# autoroute.net
KiCad netlist of a schematic drawn in EAGLE
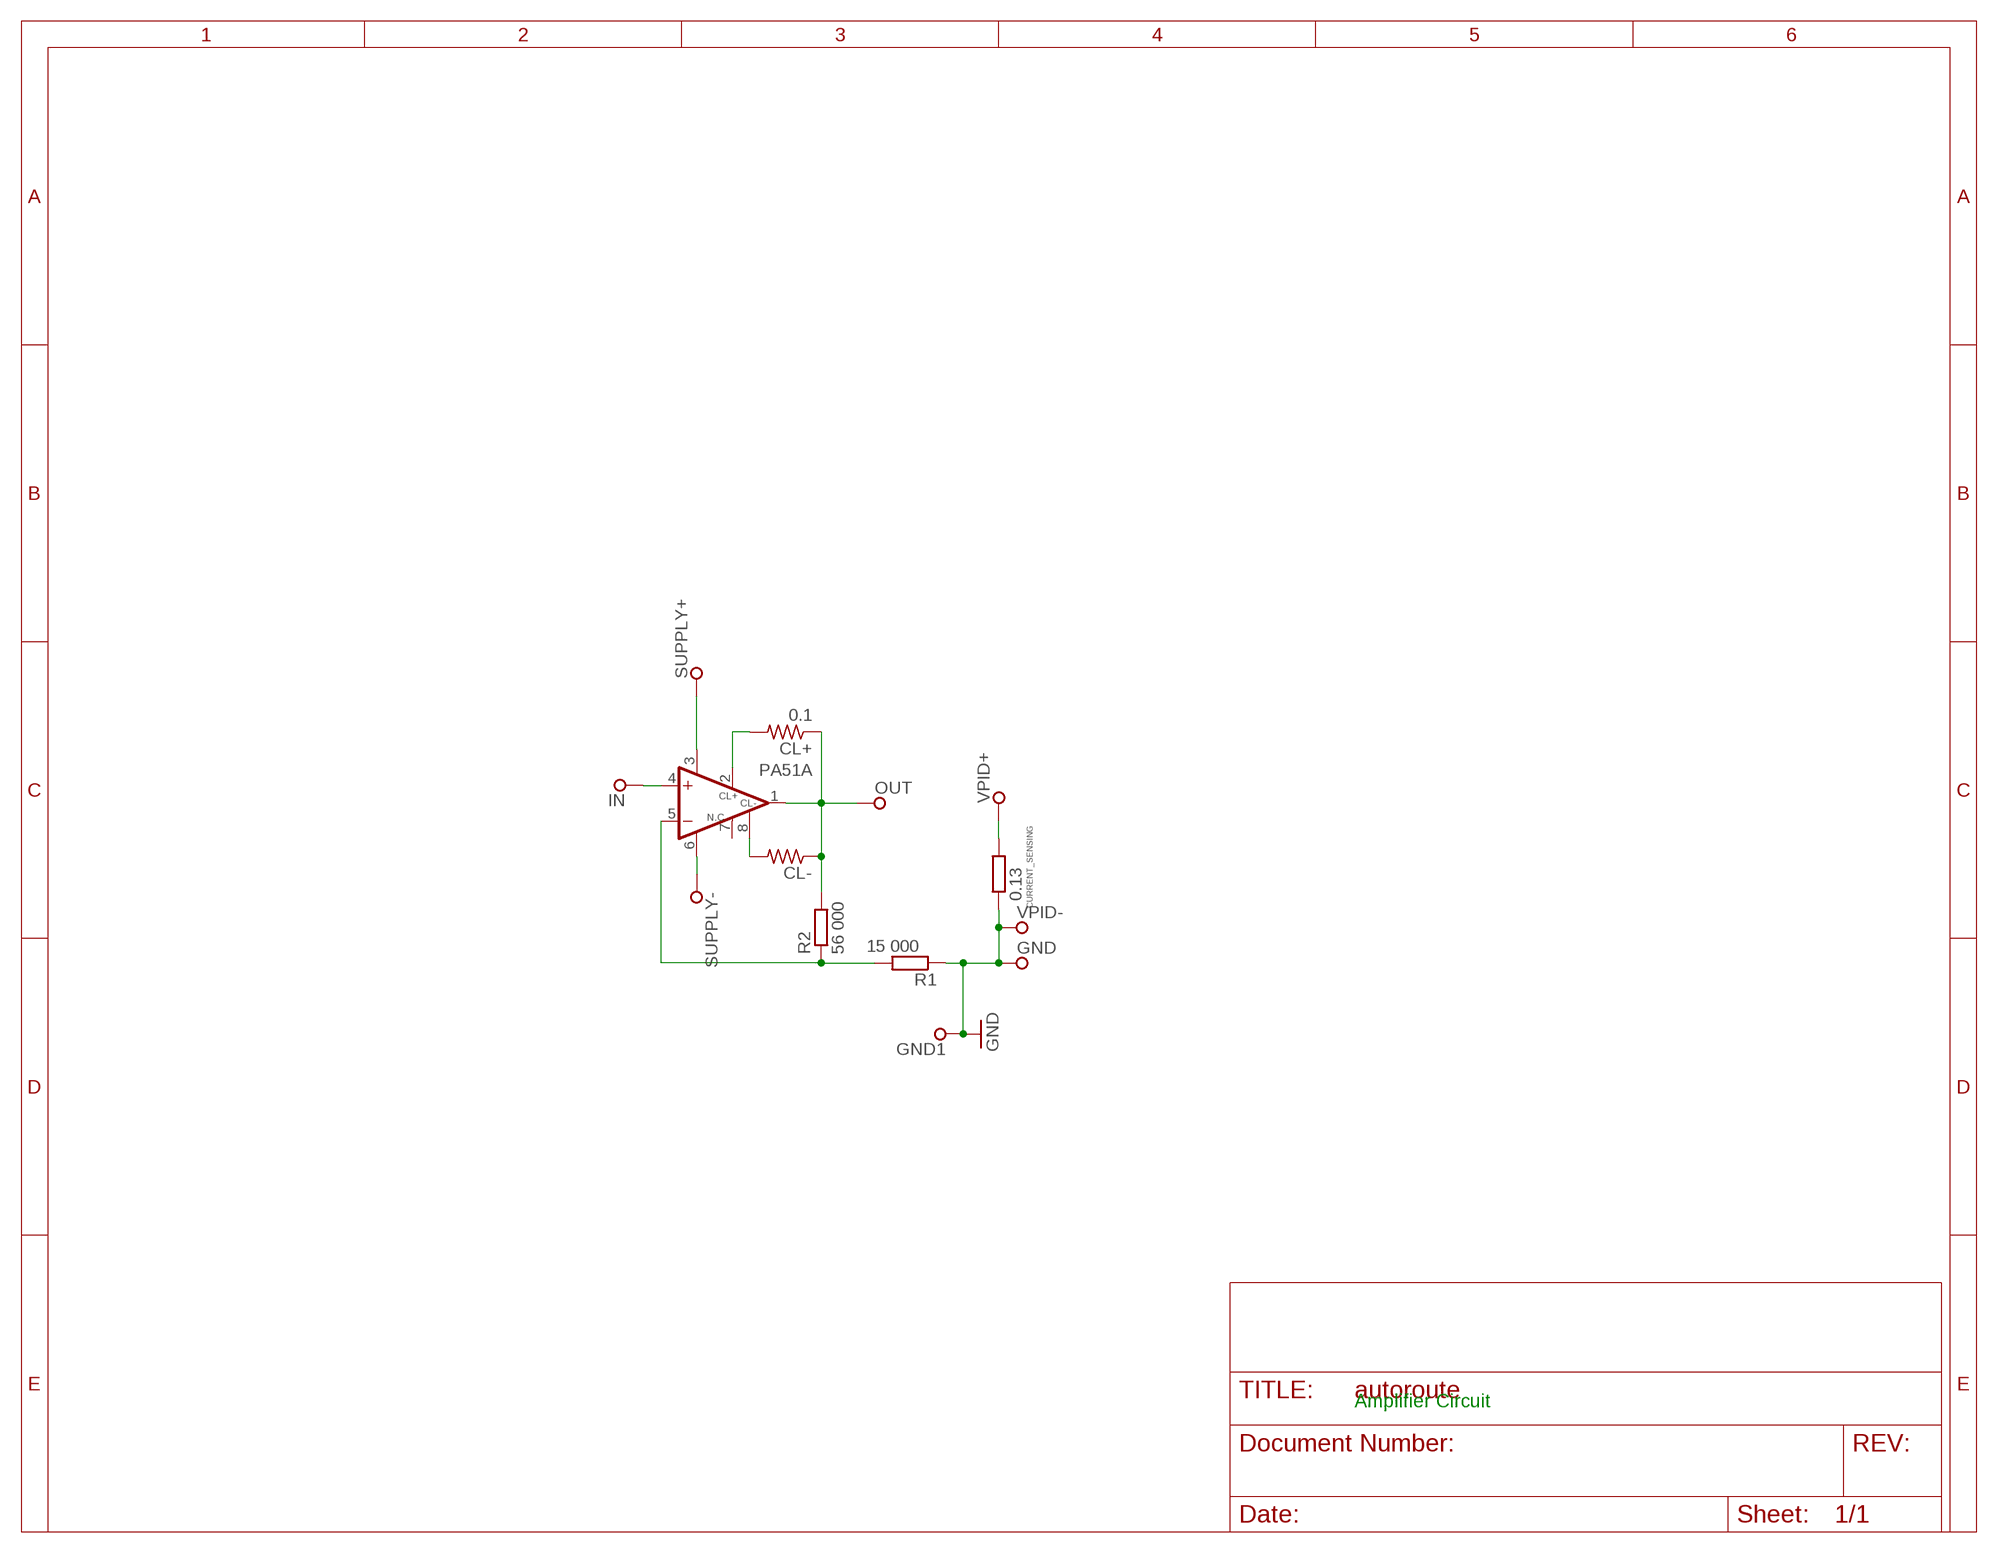
[diagram p0: schematic, sheet 1]

(export (version "E")
  (design (tool "Eeschema 10.0.6"))
  (components
    (comp (ref "CL+")
      (value "0.1")
      (footprint "eagle-import:VTA56")
      (libsource (lib "eagle-import") (part "R-US_VTA56"))
    )
    (comp (ref "CL-")
      (value "R-US_VTA56")
      (footprint "eagle-import:VTA56")
      (libsource (lib "eagle-import") (part "R-US_VTA56"))
    )
    (comp (ref "CURRENT_SENSING")
      (value "0.13")
      (footprint "eagle-import:V234_12")
      (libsource (lib "eagle-import") (part "R-EU_V234/12"))
    )
    (comp (ref "GND")
      (value "SPECIAL_DRILL_0.2500")
      (footprint "eagle-import:PAD_0.2500")
      (libsource (lib "eagle-import") (part "SPECIAL_DRILL_0.2500"))
    )
    (comp (ref "GND1")
      (value "SPECIAL_DRILL_0.2500")
      (footprint "eagle-import:PAD_0.2500")
      (libsource (lib "eagle-import") (part "SPECIAL_DRILL_0.2500"))
    )
    (comp (ref "IN")
      (value "SPECIAL_DRILL_0.2500")
      (footprint "eagle-import:PAD_0.2500")
      (libsource (lib "eagle-import") (part "SPECIAL_DRILL_0.2500"))
    )
    (comp (ref "OUT")
      (value "SPECIAL_DRILL_0.2500")
      (footprint "eagle-import:PAD_0.2500")
      (libsource (lib "eagle-import") (part "SPECIAL_DRILL_0.2500"))
    )
    (comp (ref "R1")
      (value "15 000")
      (footprint "eagle-import:V234_12")
      (libsource (lib "eagle-import") (part "R-EU_V234/12"))
    )
    (comp (ref "R2")
      (value "56 000")
      (footprint "eagle-import:V234_12")
      (libsource (lib "eagle-import") (part "R-EU_V234/12"))
    )
    (comp (ref "SUPPLY+")
      (value "SPECIAL_DRILL_0.2500")
      (footprint "eagle-import:PAD_0.2500")
      (libsource (lib "eagle-import") (part "SPECIAL_DRILL_0.2500"))
    )
    (comp (ref "SUPPLY-")
      (value "SPECIAL_DRILL_0.2500")
      (footprint "eagle-import:PAD_0.2500")
      (libsource (lib "eagle-import") (part "SPECIAL_DRILL_0.2500"))
    )
    (comp (ref "U$1")
      (value "PA51A")
      (footprint "eagle-import:0804MC")
      (libsource (lib "eagle-import") (part "PA51A"))
    )
    (comp (ref "VPID+")
      (value "SPECIAL_DRILL_0.2500")
      (footprint "eagle-import:PAD_0.2500")
      (libsource (lib "eagle-import") (part "SPECIAL_DRILL_0.2500"))
    )
    (comp (ref "VPID-")
      (value "SPECIAL_DRILL_0.2500")
      (footprint "eagle-import:PAD_0.2500")
      (libsource (lib "eagle-import") (part "SPECIAL_DRILL_0.2500"))
    )
  )
  (nets
    (net (code "1") (name "GND") (class "Default")
      (node (ref "CURRENT_SENSING") (pin "1") (pinfunction "1_1") (pintype "passive"))
      (node (ref "GND") (pin "1") (pinfunction "1_1") (pintype "passive"))
      (node (ref "GND1") (pin "1") (pinfunction "1_1") (pintype "passive"))
      (node (ref "R1") (pin "1") (pinfunction "1_1") (pintype "passive"))
      (node (ref "VPID-") (pin "1") (pinfunction "1_1") (pintype "passive"))
    )
    (net (code "2") (name "Net-(CURRENT_SENSING-Pad2)") (class "Default")
      (node (ref "CURRENT_SENSING") (pin "2") (pinfunction "2_2") (pintype "passive"))
      (node (ref "VPID+") (pin "1") (pinfunction "1_1") (pintype "passive"))
    )
    (net (code "3") (name "Net-(U$1-+IN)") (class "Default")
      (node (ref "IN") (pin "1") (pinfunction "1_1") (pintype "passive"))
      (node (ref "U$1") (pin "4") (pinfunction "+IN_4") (pintype "input"))
    )
    (net (code "4") (name "Net-(U$1--IN)") (class "Default")
      (node (ref "R1") (pin "2") (pinfunction "2_2") (pintype "passive"))
      (node (ref "R2") (pin "1") (pinfunction "1_1") (pintype "passive"))
      (node (ref "U$1") (pin "5") (pinfunction "-IN_5") (pintype "input"))
    )
    (net (code "5") (name "Net-(U$1-CL+)") (class "Default")
      (node (ref "CL+") (pin "2") (pinfunction "2_2") (pintype "passive"))
      (node (ref "U$1") (pin "2") (pinfunction "CL+_2") (pintype "input"))
    )
    (net (code "6") (name "Net-(U$1-CL-)") (class "Default")
      (node (ref "CL-") (pin "2") (pinfunction "2_2") (pintype "passive"))
      (node (ref "U$1") (pin "8") (pinfunction "CL-_8") (pintype "input"))
    )
    (net (code "7") (name "Net-(U$1-OUT)") (class "Default")
      (node (ref "CL+") (pin "1") (pinfunction "1_1") (pintype "passive"))
      (node (ref "CL-") (pin "1") (pinfunction "1_1") (pintype "passive"))
      (node (ref "OUT") (pin "1") (pinfunction "1_1") (pintype "passive"))
      (node (ref "R2") (pin "2") (pinfunction "2_2") (pintype "passive"))
      (node (ref "U$1") (pin "1") (pinfunction "OUT_1") (pintype "output"))
    )
    (net (code "8") (name "Net-(U$1-V+)") (class "Default")
      (node (ref "SUPPLY+") (pin "1") (pinfunction "1_1") (pintype "passive"))
      (node (ref "U$1") (pin "3") (pinfunction "V+_3") (pintype "power_in"))
    )
    (net (code "9") (name "Net-(U$1-V-)") (class "Default")
      (node (ref "SUPPLY-") (pin "1") (pinfunction "1_1") (pintype "passive"))
      (node (ref "U$1") (pin "6") (pinfunction "V-_6") (pintype "power_in"))
    )
    (net (code "10") (name "unconnected-(U$1-NC-Pad7)") (class "Default")
      (node (ref "U$1") (pin "7") (pinfunction "NC_7") (pintype "input"))
    )
  )
)
